# daq-beaglebone.net
KiCad netlist of a schematic drawn in EAGLE
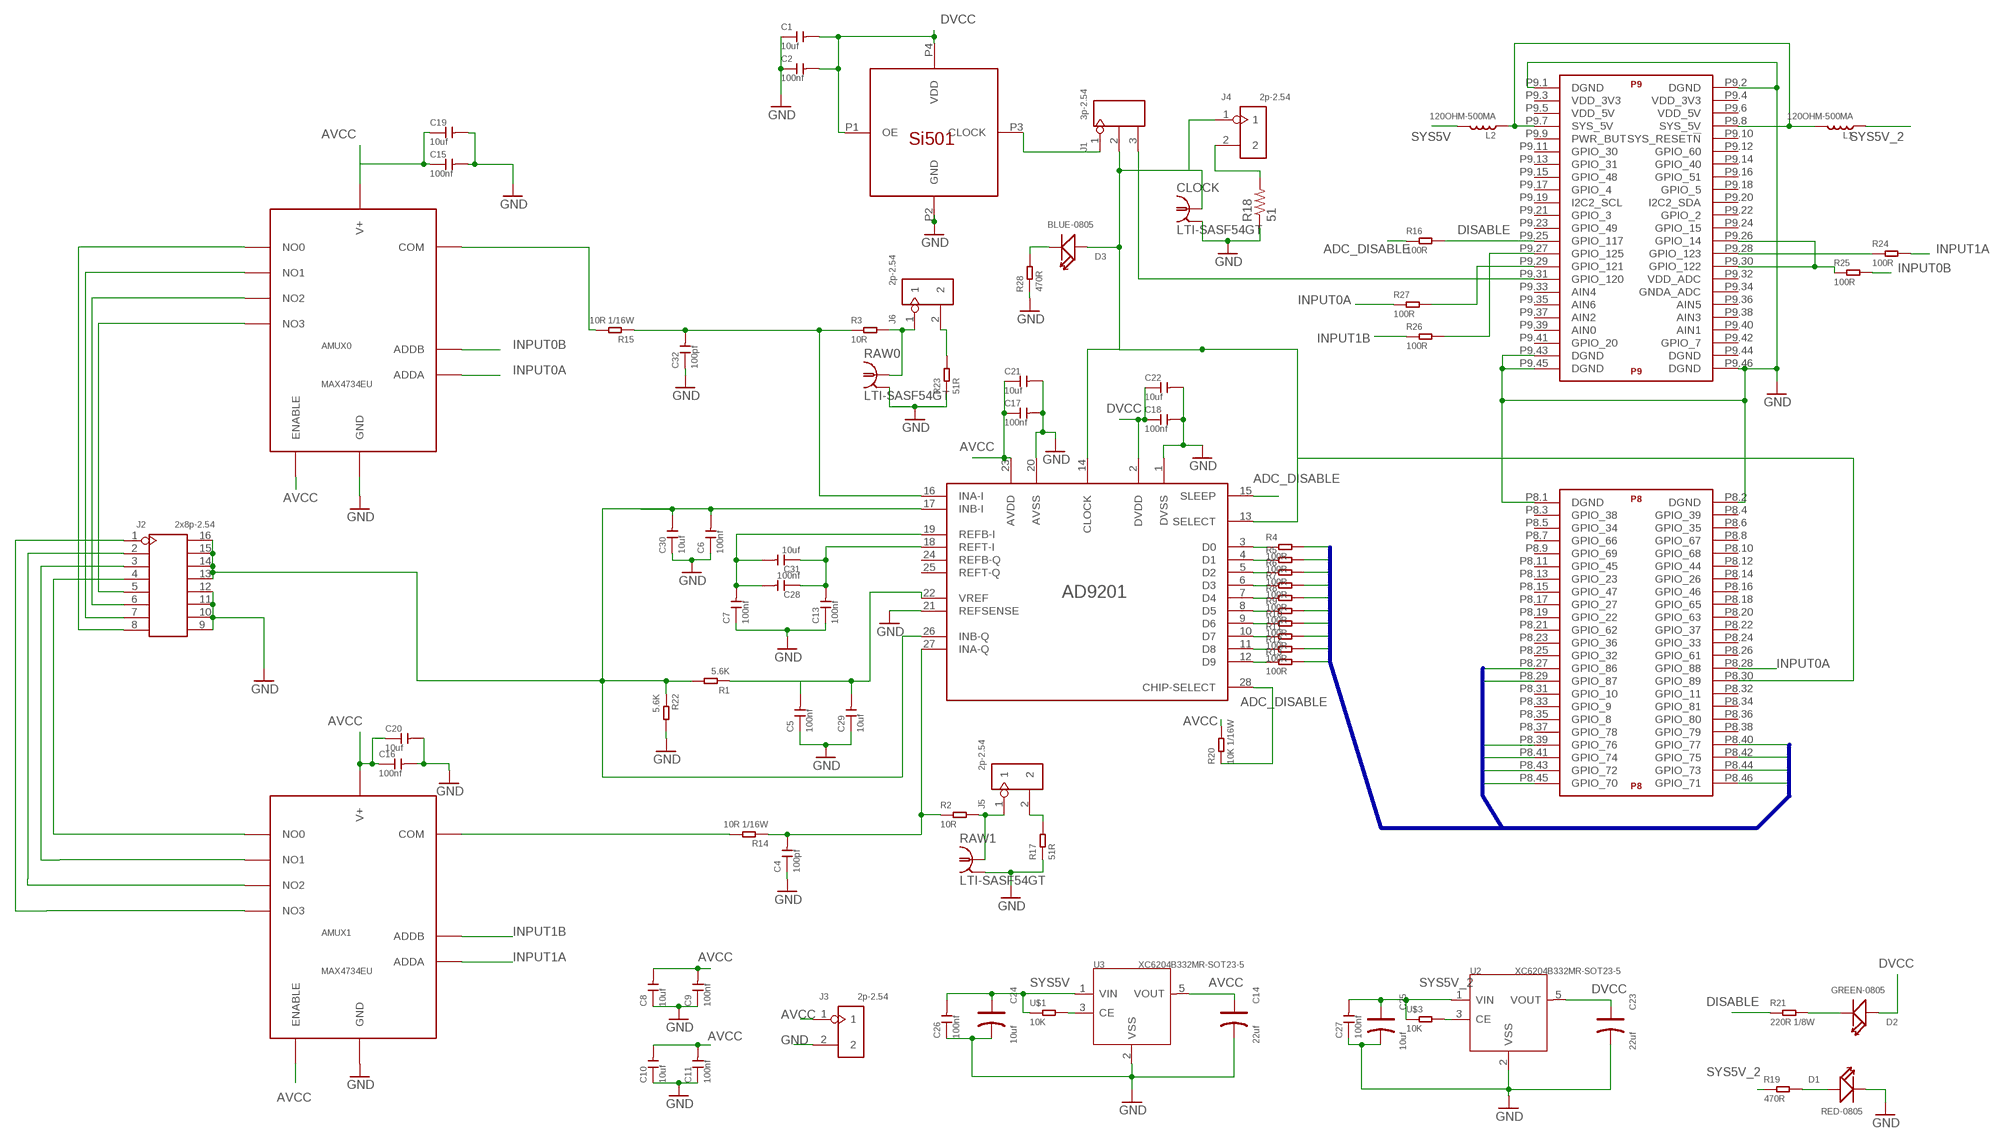
[diagram p0: schematic, sheet 1]

(export (version "E")
  (design (tool "Eeschema 10.0.6"))
  (components
    (comp (ref "AD9201")
      (value "AD9201")
      (footprint "eagle-import:SSOP28")
      (libsource (lib "eagle-import") (part "AD9201"))
    )
    (comp (ref "AMUX0")
      (value "MAX4734EU")
      (footprint "eagle-import:UMAX10")
      (libsource (lib "eagle-import") (part "MAX4734EU"))
    )
    (comp (ref "AMUX1")
      (value "MAX4734EU")
      (footprint "eagle-import:UMAX10")
      (libsource (lib "eagle-import") (part "MAX4734EU"))
    )
    (comp (ref "C1")
      (value "10uf")
      (footprint "eagle-import:C0402")
      (fields (field (name "MPN") "CC0402MRX5R5BB106"))
      (libsource (lib "eagle-import") (part "CERAMIC-10UF-6.3V-20%-X5R(0402)"))
    )
    (comp (ref "C2")
      (value "100nf")
      (footprint "eagle-import:C0402")
      (fields (field (name "MPN") "CC0402KRX7R8BB104"))
      (libsource (lib "eagle-import") (part "CERAMIC-100NF-25V-10%-X7R(0402)"))
    )
    (comp (ref "C4")
      (value "100pf")
      (footprint "eagle-import:C0402")
      (fields (field (name "MPN") "CC0402JRNPO9BN101"))
      (libsource (lib "eagle-import") (part "CERAMIC-100PF-50V-5%-NPO(0402)"))
    )
    (comp (ref "C5")
      (value "100nf")
      (footprint "eagle-import:C0402")
      (fields (field (name "MPN") "CC0402KRX7R8BB104"))
      (libsource (lib "eagle-import") (part "CERAMIC-100NF-25V-10%-X7R(0402)"))
    )
    (comp (ref "C6")
      (value "100nf")
      (footprint "eagle-import:C0402")
      (fields (field (name "MPN") "CC0402KRX7R8BB104"))
      (libsource (lib "eagle-import") (part "CERAMIC-100NF-25V-10%-X7R(0402)"))
    )
    (comp (ref "C7")
      (value "100nf")
      (footprint "eagle-import:C0402")
      (fields (field (name "MPN") "CC0402KRX7R8BB104"))
      (libsource (lib "eagle-import") (part "CERAMIC-100NF-25V-10%-X7R(0402)"))
    )
    (comp (ref "C8")
      (value "10uf")
      (footprint "eagle-import:C0402")
      (fields (field (name "MPN") "CC0402MRX5R5BB106"))
      (libsource (lib "eagle-import") (part "CERAMIC-10UF-6.3V-20%-X5R(0402)"))
    )
    (comp (ref "C9")
      (value "100nf")
      (footprint "eagle-import:C0402")
      (fields (field (name "MPN") "CC0402KRX7R8BB104"))
      (libsource (lib "eagle-import") (part "CERAMIC-100NF-25V-10%-X7R(0402)"))
    )
    (comp (ref "C10")
      (value "10uf")
      (footprint "eagle-import:C0402")
      (fields (field (name "MPN") "CC0402MRX5R5BB106"))
      (libsource (lib "eagle-import") (part "CERAMIC-10UF-6.3V-20%-X5R(0402)"))
    )
    (comp (ref "C11")
      (value "100nf")
      (footprint "eagle-import:C0402")
      (fields (field (name "MPN") "CC0402KRX7R8BB104"))
      (libsource (lib "eagle-import") (part "CERAMIC-100NF-25V-10%-X7R(0402)"))
    )
    (comp (ref "C13")
      (value "100nf")
      (footprint "eagle-import:C0402")
      (fields (field (name "MPN") "CC0402KRX7R8BB104"))
      (libsource (lib "eagle-import") (part "CERAMIC-100NF-25V-10%-X7R(0402)"))
    )
    (comp (ref "C14")
      (value "22uf")
      (footprint "eagle-import:AVX-A")
      (fields (field (name "MPN") "TAJA226K006RNJ"))
      (libsource (lib "eagle-import") (part "TANTALUM-SMD-22UF-6.3V(AVX-A)"))
    )
    (comp (ref "C15")
      (value "100nf")
      (footprint "eagle-import:C0402")
      (fields (field (name "MPN") "CC0402KRX7R8BB104"))
      (libsource (lib "eagle-import") (part "CERAMIC-100NF-25V-10%-X7R(0402)"))
    )
    (comp (ref "C16")
      (value "100nf")
      (footprint "eagle-import:C0402")
      (fields (field (name "MPN") "CC0402KRX7R8BB104"))
      (libsource (lib "eagle-import") (part "CERAMIC-100NF-25V-10%-X7R(0402)"))
    )
    (comp (ref "C17")
      (value "100nf")
      (footprint "eagle-import:C0402")
      (fields (field (name "MPN") "CC0402KRX7R8BB104"))
      (libsource (lib "eagle-import") (part "CERAMIC-100NF-25V-10%-X7R(0402)"))
    )
    (comp (ref "C18")
      (value "100nf")
      (footprint "eagle-import:C0402")
      (fields (field (name "MPN") "CC0402KRX7R8BB104"))
      (libsource (lib "eagle-import") (part "CERAMIC-100NF-25V-10%-X7R(0402)"))
    )
    (comp (ref "C19")
      (value "10uf")
      (footprint "eagle-import:C0402")
      (fields (field (name "MPN") "CC0402MRX5R5BB106"))
      (libsource (lib "eagle-import") (part "CERAMIC-10UF-6.3V-20%-X5R(0402)"))
    )
    (comp (ref "C20")
      (value "10uf")
      (footprint "eagle-import:C0402")
      (fields (field (name "MPN") "CC0402MRX5R5BB106"))
      (libsource (lib "eagle-import") (part "CERAMIC-10UF-6.3V-20%-X5R(0402)"))
    )
    (comp (ref "C21")
      (value "10uf")
      (footprint "eagle-import:C0402")
      (fields (field (name "MPN") "CC0402MRX5R5BB106"))
      (libsource (lib "eagle-import") (part "CERAMIC-10UF-6.3V-20%-X5R(0402)"))
    )
    (comp (ref "C22")
      (value "10uf")
      (footprint "eagle-import:C0402")
      (fields (field (name "MPN") "CC0402MRX5R5BB106"))
      (libsource (lib "eagle-import") (part "CERAMIC-10UF-6.3V-20%-X5R(0402)"))
    )
    (comp (ref "C23")
      (value "22uf")
      (footprint "eagle-import:AVX-A")
      (fields (field (name "MPN") "TAJA226K006RNJ"))
      (libsource (lib "eagle-import") (part "TANTALUM-SMD-22UF-6.3V(AVX-A)"))
    )
    (comp (ref "C24")
      (value "10uf")
      (footprint "eagle-import:AVX-A")
      (fields (field (name "MPN") "TAJA106K010RNJ"))
      (libsource (lib "eagle-import") (part "TANTALUM-SMD-10UF-10V-10%(AVX-A)"))
    )
    (comp (ref "C25")
      (value "10uf")
      (footprint "eagle-import:AVX-A")
      (fields (field (name "MPN") "TAJA106K010RNJ"))
      (libsource (lib "eagle-import") (part "TANTALUM-SMD-10UF-10V-10%(AVX-A)"))
    )
    (comp (ref "C26")
      (value "100nf")
      (footprint "eagle-import:C0402")
      (fields (field (name "MPN") "CC0402KRX7R8BB104"))
      (libsource (lib "eagle-import") (part "CERAMIC-100NF-25V-10%-X7R(0402)"))
    )
    (comp (ref "C27")
      (value "100nf")
      (footprint "eagle-import:C0402")
      (fields (field (name "MPN") "CC0402KRX7R8BB104"))
      (libsource (lib "eagle-import") (part "CERAMIC-100NF-25V-10%-X7R(0402)"))
    )
    (comp (ref "C28")
      (value "100nf")
      (footprint "eagle-import:C0402")
      (fields (field (name "MPN") "CC0402KRX7R8BB104"))
      (libsource (lib "eagle-import") (part "CERAMIC-100NF-25V-10%-X7R(0402)"))
    )
    (comp (ref "C29")
      (value "10uf")
      (footprint "eagle-import:C0402")
      (fields (field (name "MPN") "CC0402MRX5R5BB106"))
      (libsource (lib "eagle-import") (part "CERAMIC-10UF-6.3V-20%-X5R(0402)"))
    )
    (comp (ref "C30")
      (value "10uf")
      (footprint "eagle-import:C0402")
      (fields (field (name "MPN") "CC0402MRX5R5BB106"))
      (libsource (lib "eagle-import") (part "CERAMIC-10UF-6.3V-20%-X5R(0402)"))
    )
    (comp (ref "C31")
      (value "10uf")
      (footprint "eagle-import:C0402")
      (fields (field (name "MPN") "CC0402MRX5R5BB106"))
      (libsource (lib "eagle-import") (part "CERAMIC-10UF-6.3V-20%-X5R(0402)"))
    )
    (comp (ref "C32")
      (value "100pf")
      (footprint "eagle-import:C0402")
      (fields (field (name "MPN") "CC0402JRNPO9BN101"))
      (libsource (lib "eagle-import") (part "CERAMIC-100PF-50V-5%-NPO(0402)"))
    )
    (comp (ref "CLOCK")
      (value "LTI-SASF54GT")
      (footprint "eagle-import:LTI-SASF54GT")
      (libsource (lib "eagle-import") (part "LTI-SASF54GT"))
    )
    (comp (ref "D1")
      (value "RED-0805")
      (footprint "eagle-import:LED-0805")
      (fields (field (name "MPN") "17-215SURC/S530-A2/TR8"))
      (libsource (lib "eagle-import") (part "SMD-LED-CLEAR-RED(0805)"))
    )
    (comp (ref "D2")
      (value "GREEN-0805")
      (footprint "eagle-import:LED-0805")
      (fields (field (name "MPN") "17-215SYGC/S530-E2/TR8"))
      (libsource (lib "eagle-import") (part "SMD-LED-CLEAR-GREEN(0805)"))
    )
    (comp (ref "D3")
      (value "BLUE-0805")
      (footprint "eagle-import:LED-0805")
      (fields (field (name "MPN") "17-215SURC/S530-A2/TR8"))
      (libsource (lib "eagle-import") (part "SMD-LED-CLEAR-RED(0805)"))
    )
    (comp (ref "J1")
      (value "3p-2.54")
      (footprint "eagle-import:H3-2.54")
      (fields (field (name "MPN") "F185-1103A0BSYA1"))
      (libsource (lib "eagle-import") (part "DIP-BLACK-FEMALE-HEADER-VERT(3P-2.54)"))
    )
    (comp (ref "J2")
      (value "2x8p-2.54")
      (footprint "eagle-import:H2X8-2.54")
      (fields (field (name "MPN") "F185-1216A0BSYA1"))
      (libsource (lib "eagle-import") (part "DIP-BLACK-FEMALE-HEADER-VERT(2X8P-2.54)"))
    )
    (comp (ref "J3")
      (value "2p-2.54")
      (footprint "eagle-import:H2-2.54")
      (fields (field (name "MPN") "F185-1102A1BSYA1"))
      (libsource (lib "eagle-import") (part "DIP-BLACK-FEMALE-HEADER-VERT(2P-2.54)"))
    )
    (comp (ref "J4")
      (value "2p-2.54")
      (footprint "eagle-import:H2-2.54")
      (fields (field (name "MPN") "P125-1102A0BS116A1"))
      (libsource (lib "eagle-import") (part "DIP-BLACK-MALE-HEADER-VERT(2P-2.54)"))
    )
    (comp (ref "J5")
      (value "2p-2.54")
      (footprint "eagle-import:H2-2.54")
      (fields (field (name "MPN") "P125-1102A0BS116A1"))
      (libsource (lib "eagle-import") (part "DIP-BLACK-MALE-HEADER-VERT(2P-2.54)"))
    )
    (comp (ref "J6")
      (value "2p-2.54")
      (footprint "eagle-import:H2-2.54")
      (fields (field (name "MPN") "P125-1102A0BS116A1"))
      (libsource (lib "eagle-import") (part "DIP-BLACK-MALE-HEADER-VERT(2P-2.54)"))
    )
    (comp (ref "L1")
      (value "120OHM-500MA")
      (footprint "eagle-import:L0603")
      (fields (field (name "MPN") "BLM18AG121SN1D"))
      (libsource (lib "eagle-import") (part "SMD-FERRITE-CHIP-120-OHM-500MA(0603)"))
    )
    (comp (ref "L2")
      (value "120OHM-500MA")
      (footprint "eagle-import:L0603")
      (fields (field (name "MPN") "BLM18AG121SN1D"))
      (libsource (lib "eagle-import") (part "SMD-FERRITE-CHIP-120-OHM-500MA(0603)"))
    )
    (comp (ref "R1")
      (value "5.6K")
      (footprint "eagle-import:R0402")
      (fields (field (name "MPN") "CRCW04025K60FKED"))
      (libsource (lib "eagle-import") (part "SMD-RES-5.6K-1%-1/10W(0402)"))
    )
    (comp (ref "R2")
      (value "10R")
      (footprint "eagle-import:R0402")
      (fields (field (name "MPN") "RC0402JR-070RL"))
      (libsource (lib "eagle-import") (part "SMD-RES-0R-5%-1/16W(0402)"))
    )
    (comp (ref "R3")
      (value "10R")
      (footprint "eagle-import:R0402")
      (fields (field (name "MPN") "RC0402JR-070RL"))
      (libsource (lib "eagle-import") (part "SMD-RES-0R-5%-1/16W(0402)"))
    )
    (comp (ref "R4")
      (value "100R")
      (footprint "eagle-import:R0402")
      (fields (field (name "MPN") "RC0402JR-07100RL"))
      (libsource (lib "eagle-import") (part "SMD-RES-100R-5%-1/16W(0402)"))
    )
    (comp (ref "R5")
      (value "100R")
      (footprint "eagle-import:R0402")
      (fields (field (name "MPN") "RC0402JR-07100RL"))
      (libsource (lib "eagle-import") (part "SMD-RES-100R-5%-1/16W(0402)"))
    )
    (comp (ref "R6")
      (value "100R")
      (footprint "eagle-import:R0402")
      (fields (field (name "MPN") "RC0402JR-07100RL"))
      (libsource (lib "eagle-import") (part "SMD-RES-100R-5%-1/16W(0402)"))
    )
    (comp (ref "R7")
      (value "100R")
      (footprint "eagle-import:R0402")
      (fields (field (name "MPN") "RC0402JR-07100RL"))
      (libsource (lib "eagle-import") (part "SMD-RES-100R-5%-1/16W(0402)"))
    )
    (comp (ref "R8")
      (value "100R")
      (footprint "eagle-import:R0402")
      (fields (field (name "MPN") "RC0402JR-07100RL"))
      (libsource (lib "eagle-import") (part "SMD-RES-100R-5%-1/16W(0402)"))
    )
    (comp (ref "R9")
      (value "100R")
      (footprint "eagle-import:R0402")
      (fields (field (name "MPN") "RC0402JR-07100RL"))
      (libsource (lib "eagle-import") (part "SMD-RES-100R-5%-1/16W(0402)"))
    )
    (comp (ref "R10")
      (value "100R")
      (footprint "eagle-import:R0402")
      (fields (field (name "MPN") "RC0402JR-07100RL"))
      (libsource (lib "eagle-import") (part "SMD-RES-100R-5%-1/16W(0402)"))
    )
    (comp (ref "R11")
      (value "100R")
      (footprint "eagle-import:R0402")
      (fields (field (name "MPN") "RC0402JR-07100RL"))
      (libsource (lib "eagle-import") (part "SMD-RES-100R-5%-1/16W(0402)"))
    )
    (comp (ref "R12")
      (value "100R")
      (footprint "eagle-import:R0402")
      (fields (field (name "MPN") "RC0402JR-07100RL"))
      (libsource (lib "eagle-import") (part "SMD-RES-100R-5%-1/16W(0402)"))
    )
    (comp (ref "R13")
      (value "100R")
      (footprint "eagle-import:R0402")
      (fields (field (name "MPN") "RC0402JR-07100RL"))
      (libsource (lib "eagle-import") (part "SMD-RES-100R-5%-1/16W(0402)"))
    )
    (comp (ref "R14")
      (value "10R 1/16W")
      (footprint "eagle-import:R0402")
      (fields (field (name "MPN") "RC0402FR-0710RL"))
      (libsource (lib "eagle-import") (part "SMD-RES-10R-1%-1/16W(0402)"))
    )
    (comp (ref "R15")
      (value "10R 1/16W")
      (footprint "eagle-import:R0402")
      (fields (field (name "MPN") "RC0402FR-0710RL"))
      (libsource (lib "eagle-import") (part "SMD-RES-10R-1%-1/16W(0402)"))
    )
    (comp (ref "R16")
      (value "100R")
      (footprint "eagle-import:R0402")
      (fields (field (name "MPN") "RC0402JR-07100RL"))
      (libsource (lib "eagle-import") (part "SMD-RES-100R-5%-1/16W(0402)"))
    )
    (comp (ref "R17")
      (value "51R")
      (footprint "eagle-import:R0603")
      (fields (field (name "MPN") "RC0603FR-0751RL"))
      (libsource (lib "eagle-import") (part "SMD-RES-51R-1%-1/10W(0603)"))
    )
    (comp (ref "R18")
      (value "51")
      (footprint "eagle-import:R1206")
      (libsource (lib "eagle-import") (part "R-US_R1206"))
    )
    (comp (ref "R19")
      (value "470R")
      (footprint "eagle-import:R0402")
      (fields (field (name "MPN") "RC0402FR-07470RL"))
      (libsource (lib "eagle-import") (part "SMD-RES-470R-1%-1/16W(0402)"))
    )
    (comp (ref "R20")
      (value "10K 1/16W")
      (footprint "eagle-import:R0402")
      (fields (field (name "MPN") "RC0402FR-0710KL"))
      (libsource (lib "eagle-import") (part "SMD-RES-10K-1%-1/16W(0402)"))
    )
    (comp (ref "R21")
      (value "220R 1/8W")
      (footprint "eagle-import:R0402")
      (fields (field (name "MPN") "RC0402FR-07220RL"))
      (libsource (lib "eagle-import") (part "SMD-RES-220R-1%-1/8W(0402)"))
    )
    (comp (ref "R22")
      (value "5.6K")
      (footprint "eagle-import:R0402")
      (fields (field (name "MPN") "CRCW04025K60FKED"))
      (libsource (lib "eagle-import") (part "SMD-RES-5.6K-1%-1/10W(0402)"))
    )
    (comp (ref "R23")
      (value "51R")
      (footprint "eagle-import:R0603")
      (fields (field (name "MPN") "RC0603FR-0751RL"))
      (libsource (lib "eagle-import") (part "SMD-RES-51R-1%-1/10W(0603)"))
    )
    (comp (ref "R24")
      (value "100R")
      (footprint "eagle-import:R0402")
      (fields (field (name "MPN") "RC0402FR-0733RL"))
      (libsource (lib "eagle-import") (part "SMD-RES-33R-1%-1/16W(0402)"))
    )
    (comp (ref "R25")
      (value "100R")
      (footprint "eagle-import:R0402")
      (fields (field (name "MPN") "RC0402FR-0733RL"))
      (libsource (lib "eagle-import") (part "SMD-RES-33R-1%-1/16W(0402)"))
    )
    (comp (ref "R26")
      (value "100R")
      (footprint "eagle-import:R0402")
      (fields (field (name "MPN") "RC0402FR-0733RL"))
      (libsource (lib "eagle-import") (part "SMD-RES-33R-1%-1/16W(0402)"))
    )
    (comp (ref "R27")
      (value "100R")
      (footprint "eagle-import:R0402")
      (fields (field (name "MPN") "RC0402FR-0733RL"))
      (libsource (lib "eagle-import") (part "SMD-RES-33R-1%-1/16W(0402)"))
    )
    (comp (ref "R28")
      (value "470R")
      (footprint "eagle-import:R0402")
      (fields (field (name "MPN") "RC0402FR-07470RL"))
      (libsource (lib "eagle-import") (part "SMD-RES-470R-1%-1/16W(0402)"))
    )
    (comp (ref "RAW0")
      (value "LTI-SASF54GT")
      (footprint "eagle-import:LTI-SASF54GT")
      (libsource (lib "eagle-import") (part "LTI-SASF54GT"))
    )
    (comp (ref "RAW1")
      (value "LTI-SASF54GT")
      (footprint "eagle-import:LTI-SASF54GT")
      (libsource (lib "eagle-import") (part "LTI-SASF54GT"))
    )
    (comp (ref "U$1")
      (value "10K")
      (footprint "eagle-import:R0402")
      (fields (field (name "MPN") "RC0402JR-0710KL"))
      (libsource (lib "eagle-import") (part "SMD-RES-10K-5%-1/(0402)"))
    )
    (comp (ref "U$2")
      (value "BEAGLE_BONE_BLACK_CAPE")
      (footprint "eagle-import:BEAGLE_BONE_BLACK_CAPE")
      (libsource (lib "eagle-import") (part "BEAGLE_BONE_BLACK_CAPE"))
    )
    (comp (ref "U$3")
      (value "10K")
      (footprint "eagle-import:R0402")
      (fields (field (name "MPN") "RC0402JR-0710KL"))
      (libsource (lib "eagle-import") (part "SMD-RES-10K-5%-1/(0402)"))
    )
    (comp (ref "U$4")
      (value "SI501")
      (footprint "eagle-import:2X2.5DFN")
      (libsource (lib "eagle-import") (part "SI501"))
    )
    (comp (ref "U2")
      (value "XC6204B332MR-SOT23-5")
      (footprint "eagle-import:SOT-23-5")
      (fields (field (name "MPN") "XC6204B332MR"))
      (libsource (lib "eagle-import") (part "PMIC-XC6204B332MR(SOT23-5)"))
    )
    (comp (ref "U3")
      (value "XC6204B332MR-SOT23-5")
      (footprint "eagle-import:SOT-23-5")
      (fields (field (name "MPN") "XC6204B332MR"))
      (libsource (lib "eagle-import") (part "PMIC-XC6204B332MR(SOT23-5)"))
    )
  )
  (nets
    (net (code "1") (name "/ADC_DISABLE") (class "Default")
      (node (ref "AD9201") (pin "15") (pinfunction "SLEEP_15") (pintype "input"))
      (node (ref "AD9201") (pin "28") (pinfunction "CHIP-SELECT_28") (pintype "input"))
      (node (ref "R16") (pin "1") (pinfunction "1_1") (pintype "passive"))
      (node (ref "R20") (pin "1") (pinfunction "1_1") (pintype "passive"))
    )
    (net (code "2") (name "/AVCC") (class "Default")
      (node (ref "AD9201") (pin "23") (pinfunction "AVDD_23") (pintype "power_in"))
      (node (ref "AMUX0") (pin "P$5") (pinfunction "ENABLE_P$5") (pintype "bidirectional"))
      (node (ref "AMUX0") (pin "P$6") (pinfunction "V+_P$6") (pintype "bidirectional"))
      (node (ref "AMUX1") (pin "P$5") (pinfunction "ENABLE_P$5") (pintype "bidirectional"))
      (node (ref "AMUX1") (pin "P$6") (pinfunction "V+_P$6") (pintype "bidirectional"))
      (node (ref "C10") (pin "2") (pinfunction "2_2") (pintype "passive"))
      (node (ref "C11") (pin "2") (pinfunction "2_2") (pintype "passive"))
      (node (ref "C14") (pin "+") (pinfunction "+_+") (pintype "passive"))
      (node (ref "C15") (pin "1") (pinfunction "1_1") (pintype "passive"))
      (node (ref "C16") (pin "1") (pinfunction "1_1") (pintype "passive"))
      (node (ref "C17") (pin "1") (pinfunction "1_1") (pintype "passive"))
      (node (ref "C19") (pin "1") (pinfunction "1_1") (pintype "passive"))
      (node (ref "C20") (pin "1") (pinfunction "1_1") (pintype "passive"))
      (node (ref "C21") (pin "1") (pinfunction "1_1") (pintype "passive"))
      (node (ref "C8") (pin "2") (pinfunction "2_2") (pintype "passive"))
      (node (ref "C9") (pin "2") (pinfunction "2_2") (pintype "passive"))
      (node (ref "J3") (pin "1") (pinfunction "1_1") (pintype "bidirectional"))
      (node (ref "R20") (pin "2") (pinfunction "2_2") (pintype "passive"))
      (node (ref "U3") (pin "5") (pinfunction "VOUT_5") (pintype "bidirectional"))
    )
    (net (code "3") (name "/D0") (class "Default")
      (node (ref "R4") (pin "2") (pinfunction "2_2") (pintype "passive"))
      (node (ref "U$2") (pin "P8.45") (pinfunction "GPIO_70_P8.45") (pintype "bidirectional"))
    )
    (net (code "4") (name "/D1") (class "Default")
      (node (ref "R5") (pin "2") (pinfunction "2_2") (pintype "passive"))
      (node (ref "U$2") (pin "P8.46") (pinfunction "GPIO_71_P8.46") (pintype "bidirectional"))
    )
    (net (code "5") (name "/D2") (class "Default")
      (node (ref "R6") (pin "2") (pinfunction "2_2") (pintype "passive"))
      (node (ref "U$2") (pin "P8.43") (pinfunction "GPIO_72_P8.43") (pintype "bidirectional"))
    )
    (net (code "6") (name "/D3") (class "Default")
      (node (ref "R7") (pin "2") (pinfunction "2_2") (pintype "passive"))
      (node (ref "U$2") (pin "P8.44") (pinfunction "GPIO_73_P8.44") (pintype "bidirectional"))
    )
    (net (code "7") (name "/D4") (class "Default")
      (node (ref "R8") (pin "2") (pinfunction "2_2") (pintype "passive"))
      (node (ref "U$2") (pin "P8.41") (pinfunction "GPIO_74_P8.41") (pintype "bidirectional"))
    )
    (net (code "8") (name "/D5") (class "Default")
      (node (ref "R9") (pin "2") (pinfunction "2_2") (pintype "passive"))
      (node (ref "U$2") (pin "P8.42") (pinfunction "GPIO_75_P8.42") (pintype "bidirectional"))
    )
    (net (code "9") (name "/D6") (class "Default")
      (node (ref "R10") (pin "2") (pinfunction "2_2") (pintype "passive"))
      (node (ref "U$2") (pin "P8.39") (pinfunction "GPIO_76_P8.39") (pintype "bidirectional"))
    )
    (net (code "10") (name "/D7") (class "Default")
      (node (ref "R11") (pin "2") (pinfunction "2_2") (pintype "passive"))
      (node (ref "U$2") (pin "P8.40") (pinfunction "GPIO_77_P8.40") (pintype "bidirectional"))
    )
    (net (code "11") (name "/D8") (class "Default")
      (node (ref "R12") (pin "2") (pinfunction "2_2") (pintype "passive"))
      (node (ref "U$2") (pin "P8.27") (pinfunction "GPIO_86_P8.27") (pintype "bidirectional"))
    )
    (net (code "12") (name "/D9") (class "Default")
      (node (ref "R13") (pin "2") (pinfunction "2_2") (pintype "passive"))
      (node (ref "U$2") (pin "P8.29") (pinfunction "GPIO_87_P8.29") (pintype "bidirectional"))
    )
    (net (code "13") (name "/DISABLE") (class "Default")
      (node (ref "R16") (pin "2") (pinfunction "2_2") (pintype "passive"))
      (node (ref "R21") (pin "1") (pinfunction "1_1") (pintype "passive"))
      (node (ref "U$2") (pin "P9.25") (pinfunction "GPIO_117_P9.25") (pintype "bidirectional"))
    )
    (net (code "14") (name "/DVCC") (class "Default")
      (node (ref "AD9201") (pin "2") (pinfunction "DVDD_2") (pintype "power_in"))
      (node (ref "C1") (pin "2") (pinfunction "2_2") (pintype "passive"))
      (node (ref "C18") (pin "1") (pinfunction "1_1") (pintype "passive"))
      (node (ref "C2") (pin "2") (pinfunction "2_2") (pintype "passive"))
      (node (ref "C22") (pin "1") (pinfunction "1_1") (pintype "passive"))
      (node (ref "C23") (pin "+") (pinfunction "+_+") (pintype "passive"))
      (node (ref "D2") (pin "+") (pinfunction "+_+") (pintype "passive"))
      (node (ref "U$4") (pin "P1") (pinfunction "OE_P1") (pintype "bidirectional"))
      (node (ref "U$4") (pin "P4") (pinfunction "VDD_P4") (pintype "bidirectional"))
      (node (ref "U2") (pin "5") (pinfunction "VOUT_5") (pintype "bidirectional"))
    )
    (net (code "15") (name "/INPUT0A") (class "Default")
      (node (ref "AMUX0") (pin "P$1") (pinfunction "ADDA_P$1") (pintype "bidirectional"))
      (node (ref "R27") (pin "1") (pinfunction "1_1") (pintype "passive"))
      (node (ref "U$2") (pin "P8.28") (pinfunction "GPIO_88_P8.28") (pintype "bidirectional"))
    )
    (net (code "16") (name "/INPUT0B") (class "Default")
      (node (ref "AMUX0") (pin "P$10") (pinfunction "ADDB_P$10") (pintype "bidirectional"))
      (node (ref "R25") (pin "2") (pinfunction "2_2") (pintype "passive"))
    )
    (net (code "17") (name "/INPUT1A") (class "Default")
      (node (ref "AMUX1") (pin "P$1") (pinfunction "ADDA_P$1") (pintype "bidirectional"))
      (node (ref "R24") (pin "2") (pinfunction "2_2") (pintype "passive"))
    )
    (net (code "18") (name "/INPUT1B") (class "Default")
      (node (ref "AMUX1") (pin "P$10") (pinfunction "ADDB_P$10") (pintype "bidirectional"))
      (node (ref "R26") (pin "1") (pinfunction "1_1") (pintype "passive"))
    )
    (net (code "19") (name "/SYS5V") (class "Default")
      (node (ref "C24") (pin "+") (pinfunction "+_+") (pintype "passive"))
      (node (ref "C26") (pin "2") (pinfunction "2_2") (pintype "passive"))
      (node (ref "L2") (pin "2") (pinfunction "2_2") (pintype "passive"))
      (node (ref "U$1") (pin "1") (pinfunction "1_1") (pintype "passive"))
      (node (ref "U3") (pin "1") (pinfunction "VIN_1") (pintype "bidirectional"))
    )
    (net (code "20") (name "/SYS5V_2") (class "Default")
      (node (ref "C25") (pin "+") (pinfunction "+_+") (pintype "passive"))
      (node (ref "C27") (pin "2") (pinfunction "2_2") (pintype "passive"))
      (node (ref "L1") (pin "1") (pinfunction "1_1") (pintype "passive"))
      (node (ref "R19") (pin "1") (pinfunction "1_1") (pintype "passive"))
      (node (ref "U$3") (pin "1") (pinfunction "1_1") (pintype "passive"))
      (node (ref "U2") (pin "1") (pinfunction "VIN_1") (pintype "bidirectional"))
    )
    (net (code "21") (name "GND") (class "Default")
      (node (ref "AD9201") (pin "1") (pinfunction "DVSS_1") (pintype "power_in"))
      (node (ref "AD9201") (pin "20") (pinfunction "AVSS_20") (pintype "power_in"))
      (node (ref "AD9201") (pin "21") (pinfunction "REFSENSE_21") (pintype "input"))
      (node (ref "AMUX0") (pin "P$3") (pinfunction "GND_P$3") (pintype "bidirectional"))
      (node (ref "AMUX1") (pin "P$3") (pinfunction "GND_P$3") (pintype "bidirectional"))
      (node (ref "C1") (pin "1") (pinfunction "1_1") (pintype "passive"))
      (node (ref "C10") (pin "1") (pinfunction "1_1") (pintype "passive"))
      (node (ref "C11") (pin "1") (pinfunction "1_1") (pintype "passive"))
      (node (ref "C13") (pin "1") (pinfunction "1_1") (pintype "passive"))
      (node (ref "C14") (pin "-") (pinfunction "-_-") (pintype "passive"))
      (node (ref "C15") (pin "2") (pinfunction "2_2") (pintype "passive"))
      (node (ref "C16") (pin "2") (pinfunction "2_2") (pintype "passive"))
      (node (ref "C17") (pin "2") (pinfunction "2_2") (pintype "passive"))
      (node (ref "C18") (pin "2") (pinfunction "2_2") (pintype "passive"))
      (node (ref "C19") (pin "2") (pinfunction "2_2") (pintype "passive"))
      (node (ref "C2") (pin "1") (pinfunction "1_1") (pintype "passive"))
      (node (ref "C20") (pin "2") (pinfunction "2_2") (pintype "passive"))
      (node (ref "C21") (pin "2") (pinfunction "2_2") (pintype "passive"))
      (node (ref "C22") (pin "2") (pinfunction "2_2") (pintype "passive"))
      (node (ref "C23") (pin "-") (pinfunction "-_-") (pintype "passive"))
      (node (ref "C24") (pin "-") (pinfunction "-_-") (pintype "passive"))
      (node (ref "C25") (pin "-") (pinfunction "-_-") (pintype "passive"))
      (node (ref "C26") (pin "1") (pinfunction "1_1") (pintype "passive"))
      (node (ref "C27") (pin "1") (pinfunction "1_1") (pintype "passive"))
      (node (ref "C29") (pin "1") (pinfunction "1_1") (pintype "passive"))
      (node (ref "C30") (pin "1") (pinfunction "1_1") (pintype "passive"))
      (node (ref "C32") (pin "1") (pinfunction "1_1") (pintype "passive"))
      (node (ref "C4") (pin "1") (pinfunction "1_1") (pintype "passive"))
      (node (ref "C5") (pin "1") (pinfunction "1_1") (pintype "passive"))
      (node (ref "C6") (pin "1") (pinfunction "1_1") (pintype "passive"))
      (node (ref "C7") (pin "1") (pinfunction "1_1") (pintype "passive"))
      (node (ref "C8") (pin "1") (pinfunction "1_1") (pintype "passive"))
      (node (ref "C9") (pin "1") (pinfunction "1_1") (pintype "passive"))
      (node (ref "CLOCK") (pin "2") (pinfunction "2_2") (pintype "passive"))
      (node (ref "CLOCK") (pin "3") (pinfunction "2_3") (pintype "passive"))
      (node (ref "CLOCK") (pin "4") (pinfunction "2_4") (pintype "passive"))
      (node (ref "CLOCK") (pin "5") (pinfunction "2_5") (pintype "passive"))
      (node (ref "D1") (pin "-") (pinfunction "-_-") (pintype "passive"))
      (node (ref "J2") (pin "10") (pinfunction "10_10") (pintype "bidirectional"))
      (node (ref "J2") (pin "11") (pinfunction "11_11") (pintype "bidirectional"))
      (node (ref "J2") (pin "12") (pinfunction "12_12") (pintype "bidirectional"))
      (node (ref "J2") (pin "9") (pinfunction "9_9") (pintype "bidirectional"))
      (node (ref "J3") (pin "2") (pinfunction "2_2") (pintype "bidirectional"))
      (node (ref "R17") (pin "1") (pinfunction "1_1") (pintype "passive"))
      (node (ref "R18") (pin "1") (pinfunction "1_1") (pintype "passive"))
      (node (ref "R22") (pin "2") (pinfunction "2_2") (pintype "passive"))
      (node (ref "R23") (pin "1") (pinfunction "1_1") (pintype "passive"))
      (node (ref "R28") (pin "1") (pinfunction "1_1") (pintype "passive"))
      (node (ref "RAW0") (pin "2") (pinfunction "2_2") (pintype "passive"))
      (node (ref "RAW0") (pin "3") (pinfunction "2_3") (pintype "passive"))
      (node (ref "RAW0") (pin "4") (pinfunction "2_4") (pintype "passive"))
      (node (ref "RAW0") (pin "5") (pinfunction "2_5") (pintype "passive"))
      (node (ref "RAW1") (pin "2") (pinfunction "2_2") (pintype "passive"))
      (node (ref "RAW1") (pin "3") (pinfunction "2_3") (pintype "passive"))
      (node (ref "RAW1") (pin "4") (pinfunction "2_4") (pintype "passive"))
      (node (ref "RAW1") (pin "5") (pinfunction "2_5") (pintype "passive"))
      (node (ref "U$2") (pin "P8.1") (pinfunction "DGND_P8.1") (pintype "bidirectional"))
      (node (ref "U$2") (pin "P8.2") (pinfunction "DGND_P8.2") (pintype "bidirectional"))
      (node (ref "U$2") (pin "P9.1") (pinfunction "DGND_P9.1") (pintype "bidirectional"))
      (node (ref "U$2") (pin "P9.2") (pinfunction "DGND_P9.2") (pintype "bidirectional"))
      (node (ref "U$2") (pin "P9.43") (pinfunction "DGND_P9.43") (pintype "bidirectional"))
      (node (ref "U$2") (pin "P9.45") (pinfunction "DGND_P9.45") (pintype "bidirectional"))
      (node (ref "U$2") (pin "P9.46") (pinfunction "DGND_P9.46") (pintype "bidirectional"))
      (node (ref "U$4") (pin "P2") (pinfunction "GND_P2") (pintype "bidirectional"))
      (node (ref "U2") (pin "2") (pinfunction "VSS_2") (pintype "bidirectional"))
      (node (ref "U3") (pin "2") (pinfunction "VSS_2") (pintype "bidirectional"))
    )
    (net (code "22") (name "Net-(AD9201-CLOCK)") (class "Default")
      (node (ref "AD9201") (pin "13") (pinfunction "SELECT_13") (pintype "input"))
      (node (ref "AD9201") (pin "14") (pinfunction "CLOCK_14") (pintype "input"))
      (node (ref "CLOCK") (pin "1") (pinfunction "1_1") (pintype "passive"))
      (node (ref "D3") (pin "+") (pinfunction "+_+") (pintype "passive"))
      (node (ref "J1") (pin "2") (pinfunction "P$2_2") (pintype "bidirectional"))
      (node (ref "J4") (pin "1") (pinfunction "1_1") (pintype "bidirectional"))
      (node (ref "U$2") (pin "P8.30") (pinfunction "GPIO_89_P8.30") (pintype "bidirectional"))
    )
    (net (code "23") (name "Net-(AD9201-D0)") (class "Default")
      (node (ref "AD9201") (pin "3") (pinfunction "D0_3") (pintype "output"))
      (node (ref "R4") (pin "1") (pinfunction "1_1") (pintype "passive"))
    )
    (net (code "24") (name "Net-(AD9201-D1)") (class "Default")
      (node (ref "AD9201") (pin "4") (pinfunction "D1_4") (pintype "output"))
      (node (ref "R5") (pin "1") (pinfunction "1_1") (pintype "passive"))
    )
    (net (code "25") (name "Net-(AD9201-D2)") (class "Default")
      (node (ref "AD9201") (pin "5") (pinfunction "D2_5") (pintype "output"))
      (node (ref "R6") (pin "1") (pinfunction "1_1") (pintype "passive"))
    )
    (net (code "26") (name "Net-(AD9201-D3)") (class "Default")
      (node (ref "AD9201") (pin "6") (pinfunction "D3_6") (pintype "output"))
      (node (ref "R7") (pin "1") (pinfunction "1_1") (pintype "passive"))
    )
    (net (code "27") (name "Net-(AD9201-D4)") (class "Default")
      (node (ref "AD9201") (pin "7") (pinfunction "D4_7") (pintype "output"))
      (node (ref "R8") (pin "1") (pinfunction "1_1") (pintype "passive"))
    )
    (net (code "28") (name "Net-(AD9201-D5)") (class "Default")
      (node (ref "AD9201") (pin "8") (pinfunction "D5_8") (pintype "output"))
      (node (ref "R9") (pin "1") (pinfunction "1_1") (pintype "passive"))
    )
    (net (code "29") (name "Net-(AD9201-D6)") (class "Default")
      (node (ref "AD9201") (pin "9") (pinfunction "D6_9") (pintype "output"))
      (node (ref "R10") (pin "1") (pinfunction "1_1") (pintype "passive"))
    )
    (net (code "30") (name "Net-(AD9201-D7)") (class "Default")
      (node (ref "AD9201") (pin "10") (pinfunction "D7_10") (pintype "output"))
      (node (ref "R11") (pin "1") (pinfunction "1_1") (pintype "passive"))
    )
    (net (code "31") (name "Net-(AD9201-D8)") (class "Default")
      (node (ref "AD9201") (pin "11") (pinfunction "D8_11") (pintype "output"))
      (node (ref "R12") (pin "1") (pinfunction "1_1") (pintype "passive"))
    )
    (net (code "32") (name "Net-(AD9201-D9)") (class "Default")
      (node (ref "AD9201") (pin "12") (pinfunction "D9_12") (pintype "output"))
      (node (ref "R13") (pin "1") (pinfunction "1_1") (pintype "passive"))
    )
    (net (code "33") (name "Net-(AD9201-INA-I)") (class "Default")
      (node (ref "AD9201") (pin "16") (pinfunction "INA-I_16") (pintype "input"))
      (node (ref "C32") (pin "2") (pinfunction "2_2") (pintype "passive"))
      (node (ref "R15") (pin "1") (pinfunction "1_1") (pintype "passive"))
      (node (ref "R3") (pin "1") (pinfunction "1_1") (pintype "passive"))
    )
    (net (code "34") (name "Net-(AD9201-INA-Q)") (class "Default")
      (node (ref "AD9201") (pin "27") (pinfunction "INA-Q_27") (pintype "input"))
      (node (ref "C4") (pin "2") (pinfunction "2_2") (pintype "passive"))
      (node (ref "R14") (pin "1") (pinfunction "1_1") (pintype "passive"))
      (node (ref "R2") (pin "1") (pinfunction "1_1") (pintype "passive"))
    )
    (net (code "35") (name "Net-(AD9201-INB-I)") (class "Default")
      (node (ref "AD9201") (pin "17") (pinfunction "INB-I_17") (pintype "input"))
      (node (ref "AD9201") (pin "26") (pinfunction "INB-Q_26") (pintype "input"))
      (node (ref "C30") (pin "2") (pinfunction "2_2") (pintype "passive"))
      (node (ref "C6") (pin "2") (pinfunction "2_2") (pintype "passive"))
      (node (ref "J2") (pin "13") (pinfunction "13_13") (pintype "bidirectional"))
      (node (ref "J2") (pin "14") (pinfunction "14_14") (pintype "bidirectional"))
      (node (ref "J2") (pin "15") (pinfunction "15_15") (pintype "bidirectional"))
      (node (ref "J2") (pin "16") (pinfunction "16_16") (pintype "bidirectional"))
      (node (ref "R1") (pin "2") (pinfunction "2_2") (pintype "passive"))
      (node (ref "R22") (pin "1") (pinfunction "1_1") (pintype "passive"))
    )
    (net (code "36") (name "Net-(AD9201-REFB-I)") (class "Default")
      (node (ref "AD9201") (pin "19") (pinfunction "REFB-I_19") (pintype "bidirectional"))
      (node (ref "C28") (pin "2") (pinfunction "2_2") (pintype "passive"))
      (node (ref "C31") (pin "2") (pinfunction "2_2") (pintype "passive"))
      (node (ref "C7") (pin "2") (pinfunction "2_2") (pintype "passive"))
    )
    (net (code "37") (name "Net-(AD9201-REFT-I)") (class "Default")
      (node (ref "AD9201") (pin "18") (pinfunction "REFT-I_18") (pintype "bidirectional"))
      (node (ref "C13") (pin "2") (pinfunction "2_2") (pintype "passive"))
      (node (ref "C28") (pin "1") (pinfunction "1_1") (pintype "passive"))
      (node (ref "C31") (pin "1") (pinfunction "1_1") (pintype "passive"))
    )
    (net (code "38") (name "Net-(AD9201-VREF)") (class "Default")
      (node (ref "AD9201") (pin "22") (pinfunction "VREF_22") (pintype "output"))
      (node (ref "C29") (pin "2") (pinfunction "2_2") (pintype "passive"))
      (node (ref "C5") (pin "2") (pinfunction "2_2") (pintype "passive"))
      (node (ref "R1") (pin "1") (pinfunction "1_1") (pintype "passive"))
    )
    (net (code "39") (name "Net-(AMUX0-COM)") (class "Default")
      (node (ref "AMUX0") (pin "P$8") (pinfunction "COM_P$8") (pintype "bidirectional"))
      (node (ref "R15") (pin "2") (pinfunction "2_2") (pintype "passive"))
    )
    (net (code "40") (name "Net-(AMUX0-NO0)") (class "Default")
      (node (ref "AMUX0") (pin "P$2") (pinfunction "NO0_P$2") (pintype "bidirectional"))
      (node (ref "J2") (pin "8") (pinfunction "8_8") (pintype "bidirectional"))
    )
    (net (code "41") (name "Net-(AMUX0-NO1)") (class "Default")
      (node (ref "AMUX0") (pin "P$9") (pinfunction "NO1_P$9") (pintype "bidirectional"))
      (node (ref "J2") (pin "7") (pinfunction "7_7") (pintype "bidirectional"))
    )
    (net (code "42") (name "Net-(AMUX0-NO2)") (class "Default")
      (node (ref "AMUX0") (pin "P$4") (pinfunction "NO2_P$4") (pintype "bidirectional"))
      (node (ref "J2") (pin "6") (pinfunction "6_6") (pintype "bidirectional"))
    )
    (net (code "43") (name "Net-(AMUX0-NO3)") (class "Default")
      (node (ref "AMUX0") (pin "P$7") (pinfunction "NO3_P$7") (pintype "bidirectional"))
      (node (ref "J2") (pin "5") (pinfunction "5_5") (pintype "bidirectional"))
    )
    (net (code "44") (name "Net-(AMUX1-COM)") (class "Default")
      (node (ref "AMUX1") (pin "P$8") (pinfunction "COM_P$8") (pintype "bidirectional"))
      (node (ref "R14") (pin "2") (pinfunction "2_2") (pintype "passive"))
    )
    (net (code "45") (name "Net-(AMUX1-NO0)") (class "Default")
      (node (ref "AMUX1") (pin "P$2") (pinfunction "NO0_P$2") (pintype "bidirectional"))
      (node (ref "J2") (pin "4") (pinfunction "4_4") (pintype "bidirectional"))
    )
    (net (code "46") (name "Net-(AMUX1-NO1)") (class "Default")
      (node (ref "AMUX1") (pin "P$9") (pinfunction "NO1_P$9") (pintype "bidirectional"))
      (node (ref "J2") (pin "3") (pinfunction "3_3") (pintype "bidirectional"))
    )
    (net (code "47") (name "Net-(AMUX1-NO2)") (class "Default")
      (node (ref "AMUX1") (pin "P$4") (pinfunction "NO2_P$4") (pintype "bidirectional"))
      (node (ref "J2") (pin "2") (pinfunction "2_2") (pintype "bidirectional"))
    )
    (net (code "48") (name "Net-(AMUX1-NO3)") (class "Default")
      (node (ref "AMUX1") (pin "P$7") (pinfunction "NO3_P$7") (pintype "bidirectional"))
      (node (ref "J2") (pin "1") (pinfunction "1_1") (pintype "bidirectional"))
    )
    (net (code "49") (name "Net-(D1-Pad+)") (class "Default")
      (node (ref "D1") (pin "+") (pinfunction "+_+") (pintype "passive"))
      (node (ref "R19") (pin "2") (pinfunction "2_2") (pintype "passive"))
    )
    (net (code "50") (name "Net-(D2-Pad-)") (class "Default")
      (node (ref "D2") (pin "-") (pinfunction "-_-") (pintype "passive"))
      (node (ref "R21") (pin "2") (pinfunction "2_2") (pintype "passive"))
    )
    (net (code "51") (name "Net-(D3-Pad-)") (class "Default")
      (node (ref "D3") (pin "-") (pinfunction "-_-") (pintype "passive"))
      (node (ref "R28") (pin "2") (pinfunction "2_2") (pintype "passive"))
    )
    (net (code "52") (name "Net-(J1-P$1)") (class "Default")
      (node (ref "J1") (pin "1") (pinfunction "P$1_1") (pintype "bidirectional"))
      (node (ref "U$4") (pin "P3") (pinfunction "CLOCK_P3") (pintype "bidirectional"))
    )
    (net (code "53") (name "Net-(J1-P$3)") (class "Default")
      (node (ref "J1") (pin "3") (pinfunction "P$3_3") (pintype "bidirectional"))
      (node (ref "U$2") (pin "P9.31") (pinfunction "GPIO_120_P9.31") (pintype "bidirectional"))
    )
    (net (code "54") (name "Net-(J4-Pad2)") (class "Default")
      (node (ref "J4") (pin "2") (pinfunction "2_2") (pintype "bidirectional"))
      (node (ref "R18") (pin "2") (pinfunction "2_2") (pintype "passive"))
    )
    (net (code "55") (name "Net-(J5-Pad1)") (class "Default")
      (node (ref "J5") (pin "1") (pinfunction "1_1") (pintype "bidirectional"))
      (node (ref "R2") (pin "2") (pinfunction "2_2") (pintype "passive"))
      (node (ref "RAW1") (pin "1") (pinfunction "1_1") (pintype "passive"))
    )
    (net (code "56") (name "Net-(J5-Pad2)") (class "Default")
      (node (ref "J5") (pin "2") (pinfunction "2_2") (pintype "bidirectional"))
      (node (ref "R17") (pin "2") (pinfunction "2_2") (pintype "passive"))
    )
    (net (code "57") (name "Net-(J6-Pad1)") (class "Default")
      (node (ref "J6") (pin "1") (pinfunction "1_1") (pintype "bidirectional"))
      (node (ref "R3") (pin "2") (pinfunction "2_2") (pintype "passive"))
      (node (ref "RAW0") (pin "1") (pinfunction "1_1") (pintype "passive"))
    )
    (net (code "58") (name "Net-(J6-Pad2)") (class "Default")
      (node (ref "J6") (pin "2") (pinfunction "2_2") (pintype "bidirectional"))
      (node (ref "R23") (pin "2") (pinfunction "2_2") (pintype "passive"))
    )
    (net (code "59") (name "Net-(L1-Pad2)") (class "Default")
      (node (ref "L1") (pin "2") (pinfunction "2_2") (pintype "passive"))
      (node (ref "L2") (pin "1") (pinfunction "1_1") (pintype "passive"))
      (node (ref "U$2") (pin "P9.7") (pinfunction "SYS_5V_P9.7") (pintype "bidirectional"))
      (node (ref "U$2") (pin "P9.8") (pinfunction "SYS_5V_P9.8") (pintype "bidirectional"))
    )
    (net (code "60") (name "Net-(U$2B-GPIO_121)") (class "Default")
      (node (ref "R27") (pin "2") (pinfunction "2_2") (pintype "passive"))
      (node (ref "U$2") (pin "P9.29") (pinfunction "GPIO_121_P9.29") (pintype "bidirectional"))
    )
    (net (code "61") (name "Net-(U$2B-GPIO_122)") (class "Default")
      (node (ref "R25") (pin "1") (pinfunction "1_1") (pintype "passive"))
      (node (ref "U$2") (pin "P9.26") (pinfunction "GPIO_14_P9.26") (pintype "bidirectional"))
      (node (ref "U$2") (pin "P9.30") (pinfunction "GPIO_122_P9.30") (pintype "bidirectional"))
    )
    (net (code "62") (name "Net-(U$2B-GPIO_123)") (class "Default")
      (node (ref "R24") (pin "1") (pinfunction "1_1") (pintype "passive"))
      (node (ref "U$2") (pin "P9.28") (pinfunction "GPIO_123_P9.28") (pintype "bidirectional"))
    )
    (net (code "63") (name "Net-(U$2B-GPIO_125)") (class "Default")
      (node (ref "R26") (pin "2") (pinfunction "2_2") (pintype "passive"))
      (node (ref "U$2") (pin "P9.27") (pinfunction "GPIO_125_P9.27") (pintype "bidirectional"))
    )
    (net (code "64") (name "Net-(U2-CE)") (class "Default")
      (node (ref "U$3") (pin "2") (pinfunction "2_2") (pintype "passive"))
      (node (ref "U2") (pin "3") (pinfunction "CE_3") (pintype "bidirectional"))
    )
    (net (code "65") (name "Net-(U3-CE)") (class "Default")
      (node (ref "U$1") (pin "2") (pinfunction "2_2") (pintype "passive"))
      (node (ref "U3") (pin "3") (pinfunction "CE_3") (pintype "bidirectional"))
    )
    (net (code "66") (name "unconnected-(AD9201-REFB-Q-Pad24)") (class "Default")
      (node (ref "AD9201") (pin "24") (pinfunction "REFB-Q_24") (pintype "bidirectional"))
    )
    (net (code "67") (name "unconnected-(AD9201-REFT-Q-Pad25)") (class "Default")
      (node (ref "AD9201") (pin "25") (pinfunction "REFT-Q_25") (pintype "bidirectional"))
    )
    (net (code "68") (name "unconnected-(U$2A-GPIO_8-PadP8.35)") (class "Default")
      (node (ref "U$2") (pin "P8.35") (pinfunction "GPIO_8_P8.35") (pintype "bidirectional"))
    )
    (net (code "69") (name "unconnected-(U$2A-GPIO_9-PadP8.33)") (class "Default")
      (node (ref "U$2") (pin "P8.33") (pinfunction "GPIO_9_P8.33") (pintype "bidirectional"))
    )
    (net (code "70") (name "unconnected-(U$2A-GPIO_10-PadP8.31)") (class "Default")
      (node (ref "U$2") (pin "P8.31") (pinfunction "GPIO_10_P8.31") (pintype "bidirectional"))
    )
    (net (code "71") (name "unconnected-(U$2A-GPIO_11-PadP8.32)") (class "Default")
      (node (ref "U$2") (pin "P8.32") (pinfunction "GPIO_11_P8.32") (pintype "bidirectional"))
    )
    (net (code "72") (name "unconnected-(U$2A-GPIO_22-PadP8.19)") (class "Default")
      (node (ref "U$2") (pin "P8.19") (pinfunction "GPIO_22_P8.19") (pintype "bidirectional"))
    )
    (net (code "73") (name "unconnected-(U$2A-GPIO_23-PadP8.13)") (class "Default")
      (node (ref "U$2") (pin "P8.13") (pinfunction "GPIO_23_P8.13") (pintype "bidirectional"))
    )
    (net (code "74") (name "unconnected-(U$2A-GPIO_26-PadP8.14)") (class "Default")
      (node (ref "U$2") (pin "P8.14") (pinfunction "GPIO_26_P8.14") (pintype "bidirectional"))
    )
    (net (code "75") (name "unconnected-(U$2A-GPIO_27-PadP8.17)") (class "Default")
      (node (ref "U$2") (pin "P8.17") (pinfunction "GPIO_27_P8.17") (pintype "bidirectional"))
    )
    (net (code "76") (name "unconnected-(U$2A-GPIO_32-PadP8.25)") (class "Default")
      (node (ref "U$2") (pin "P8.25") (pinfunction "GPIO_32_P8.25") (pintype "bidirectional"))
    )
    (net (code "77") (name "unconnected-(U$2A-GPIO_33-PadP8.24)") (class "Default")
      (node (ref "U$2") (pin "P8.24") (pinfunction "GPIO_33_P8.24") (pintype "bidirectional"))
    )
    (net (code "78") (name "unconnected-(U$2A-GPIO_34-PadP8.5)") (class "Default")
      (node (ref "U$2") (pin "P8.5") (pinfunction "GPIO_34_P8.5") (pintype "bidirectional"))
    )
    (net (code "79") (name "unconnected-(U$2A-GPIO_35-PadP8.6)") (class "Default")
      (node (ref "U$2") (pin "P8.6") (pinfunction "GPIO_35_P8.6") (pintype "bidirectional"))
    )
    (net (code "80") (name "unconnected-(U$2A-GPIO_36-PadP8.23)") (class "Default")
      (node (ref "U$2") (pin "P8.23") (pinfunction "GPIO_36_P8.23") (pintype "bidirectional"))
    )
    (net (code "81") (name "unconnected-(U$2A-GPIO_37-PadP8.22)") (class "Default")
      (node (ref "U$2") (pin "P8.22") (pinfunction "GPIO_37_P8.22") (pintype "bidirectional"))
    )
    (net (code "82") (name "unconnected-(U$2A-GPIO_38-PadP8.3)") (class "Default")
      (node (ref "U$2") (pin "P8.3") (pinfunction "GPIO_38_P8.3") (pintype "bidirectional"))
    )
    (net (code "83") (name "unconnected-(U$2A-GPIO_39-PadP8.4)") (class "Default")
      (node (ref "U$2") (pin "P8.4") (pinfunction "GPIO_39_P8.4") (pintype "bidirectional"))
    )
    (net (code "84") (name "unconnected-(U$2A-GPIO_44-PadP8.12)") (class "Default")
      (node (ref "U$2") (pin "P8.12") (pinfunction "GPIO_44_P8.12") (pintype "bidirectional"))
    )
    (net (code "85") (name "unconnected-(U$2A-GPIO_45-PadP8.11)") (class "Default")
      (node (ref "U$2") (pin "P8.11") (pinfunction "GPIO_45_P8.11") (pintype "bidirectional"))
    )
    (net (code "86") (name "unconnected-(U$2A-GPIO_46-PadP8.16)") (class "Default")
      (node (ref "U$2") (pin "P8.16") (pinfunction "GPIO_46_P8.16") (pintype "bidirectional"))
    )
    (net (code "87") (name "unconnected-(U$2A-GPIO_47-PadP8.15)") (class "Default")
      (node (ref "U$2") (pin "P8.15") (pinfunction "GPIO_47_P8.15") (pintype "bidirectional"))
    )
    (net (code "88") (name "unconnected-(U$2A-GPIO_61-PadP8.26)") (class "Default")
      (node (ref "U$2") (pin "P8.26") (pinfunction "GPIO_61_P8.26") (pintype "bidirectional"))
    )
    (net (code "89") (name "unconnected-(U$2A-GPIO_62-PadP8.21)") (class "Default")
      (node (ref "U$2") (pin "P8.21") (pinfunction "GPIO_62_P8.21") (pintype "bidirectional"))
    )
    (net (code "90") (name "unconnected-(U$2A-GPIO_63-PadP8.20)") (class "Default")
      (node (ref "U$2") (pin "P8.20") (pinfunction "GPIO_63_P8.20") (pintype "bidirectional"))
    )
    (net (code "91") (name "unconnected-(U$2A-GPIO_65-PadP8.18)") (class "Default")
      (node (ref "U$2") (pin "P8.18") (pinfunction "GPIO_65_P8.18") (pintype "bidirectional"))
    )
    (net (code "92") (name "unconnected-(U$2A-GPIO_66-PadP8.7)") (class "Default")
      (node (ref "U$2") (pin "P8.7") (pinfunction "GPIO_66_P8.7") (pintype "bidirectional"))
    )
    (net (code "93") (name "unconnected-(U$2A-GPIO_67-PadP8.8)") (class "Default")
      (node (ref "U$2") (pin "P8.8") (pinfunction "GPIO_67_P8.8") (pintype "bidirectional"))
    )
    (net (code "94") (name "unconnected-(U$2A-GPIO_68-PadP8.10)") (class "Default")
      (node (ref "U$2") (pin "P8.10") (pinfunction "GPIO_68_P8.10") (pintype "bidirectional"))
    )
    (net (code "95") (name "unconnected-(U$2A-GPIO_69-PadP8.9)") (class "Default")
      (node (ref "U$2") (pin "P8.9") (pinfunction "GPIO_69_P8.9") (pintype "bidirectional"))
    )
    (net (code "96") (name "unconnected-(U$2A-GPIO_78-PadP8.37)") (class "Default")
      (node (ref "U$2") (pin "P8.37") (pinfunction "GPIO_78_P8.37") (pintype "bidirectional"))
    )
    (net (code "97") (name "unconnected-(U$2A-GPIO_79-PadP8.38)") (class "Default")
      (node (ref "U$2") (pin "P8.38") (pinfunction "GPIO_79_P8.38") (pintype "bidirectional"))
    )
    (net (code "98") (name "unconnected-(U$2A-GPIO_80-PadP8.36)") (class "Default")
      (node (ref "U$2") (pin "P8.36") (pinfunction "GPIO_80_P8.36") (pintype "bidirectional"))
    )
    (net (code "99") (name "unconnected-(U$2A-GPIO_81-PadP8.34)") (class "Default")
      (node (ref "U$2") (pin "P8.34") (pinfunction "GPIO_81_P8.34") (pintype "bidirectional"))
    )
    (net (code "100") (name "unconnected-(U$2B-AIN0-PadP9.39)") (class "Default")
      (node (ref "U$2") (pin "P9.39") (pinfunction "AIN0_P9.39") (pintype "bidirectional"))
    )
    (net (code "101") (name "unconnected-(U$2B-AIN1-PadP9.40)") (class "Default")
      (node (ref "U$2") (pin "P9.40") (pinfunction "AIN1_P9.40") (pintype "bidirectional"))
    )
    (net (code "102") (name "unconnected-(U$2B-AIN2-PadP9.37)") (class "Default")
      (node (ref "U$2") (pin "P9.37") (pinfunction "AIN2_P9.37") (pintype "bidirectional"))
    )
    (net (code "103") (name "unconnected-(U$2B-AIN3-PadP9.38)") (class "Default")
      (node (ref "U$2") (pin "P9.38") (pinfunction "AIN3_P9.38") (pintype "bidirectional"))
    )
    (net (code "104") (name "unconnected-(U$2B-AIN4-PadP9.33)") (class "Default")
      (node (ref "U$2") (pin "P9.33") (pinfunction "AIN4_P9.33") (pintype "bidirectional"))
    )
    (net (code "105") (name "unconnected-(U$2B-AIN5-PadP9.36)") (class "Default")
      (node (ref "U$2") (pin "P9.36") (pinfunction "AIN5_P9.36") (pintype "bidirectional"))
    )
    (net (code "106") (name "unconnected-(U$2B-AIN6-PadP9.35)") (class "Default")
      (node (ref "U$2") (pin "P9.35") (pinfunction "AIN6_P9.35") (pintype "bidirectional"))
    )
    (net (code "107") (name "unconnected-(U$2B-DGND-PadP9.44)") (class "Default")
      (node (ref "U$2") (pin "P9.44") (pinfunction "DGND_P9.44") (pintype "bidirectional"))
    )
    (net (code "108") (name "unconnected-(U$2B-GNDA_ADC-PadP9.34)") (class "Default")
      (node (ref "U$2") (pin "P9.34") (pinfunction "GNDA_ADC_P9.34") (pintype "bidirectional"))
    )
    (net (code "109") (name "unconnected-(U$2B-GPIO_2-PadP9.22)") (class "Default")
      (node (ref "U$2") (pin "P9.22") (pinfunction "GPIO_2_P9.22") (pintype "bidirectional"))
    )
    (net (code "110") (name "unconnected-(U$2B-GPIO_3-PadP9.21)") (class "Default")
      (node (ref "U$2") (pin "P9.21") (pinfunction "GPIO_3_P9.21") (pintype "bidirectional"))
    )
    (net (code "111") (name "unconnected-(U$2B-GPIO_4-PadP9.17)") (class "Default")
      (node (ref "U$2") (pin "P9.17") (pinfunction "GPIO_4_P9.17") (pintype "bidirectional"))
    )
    (net (code "112") (name "unconnected-(U$2B-GPIO_5-PadP9.18)") (class "Default")
      (node (ref "U$2") (pin "P9.18") (pinfunction "GPIO_5_P9.18") (pintype "bidirectional"))
    )
    (net (code "113") (name "unconnected-(U$2B-GPIO_7-PadP9.42)") (class "Default")
      (node (ref "U$2") (pin "P9.42") (pinfunction "GPIO_7_P9.42") (pintype "bidirectional"))
    )
    (net (code "114") (name "unconnected-(U$2B-GPIO_15-PadP9.24)") (class "Default")
      (node (ref "U$2") (pin "P9.24") (pinfunction "GPIO_15_P9.24") (pintype "bidirectional"))
    )
    (net (code "115") (name "unconnected-(U$2B-GPIO_20-PadP9.41)") (class "Default")
      (node (ref "U$2") (pin "P9.41") (pinfunction "GPIO_20_P9.41") (pintype "bidirectional"))
    )
    (net (code "116") (name "unconnected-(U$2B-GPIO_30-PadP9.11)") (class "Default")
      (node (ref "U$2") (pin "P9.11") (pinfunction "GPIO_30_P9.11") (pintype "bidirectional"))
    )
    (net (code "117") (name "unconnected-(U$2B-GPIO_31-PadP9.13)") (class "Default")
      (node (ref "U$2") (pin "P9.13") (pinfunction "GPIO_31_P9.13") (pintype "bidirectional"))
    )
    (net (code "118") (name "unconnected-(U$2B-GPIO_40-PadP9.14)") (class "Default")
      (node (ref "U$2") (pin "P9.14") (pinfunction "GPIO_40_P9.14") (pintype "bidirectional"))
    )
    (net (code "119") (name "unconnected-(U$2B-GPIO_48-PadP9.15)") (class "Default")
      (node (ref "U$2") (pin "P9.15") (pinfunction "GPIO_48_P9.15") (pintype "bidirectional"))
    )
    (net (code "120") (name "unconnected-(U$2B-GPIO_49-PadP9.23)") (class "Default")
      (node (ref "U$2") (pin "P9.23") (pinfunction "GPIO_49_P9.23") (pintype "bidirectional"))
    )
    (net (code "121") (name "unconnected-(U$2B-GPIO_51-PadP9.16)") (class "Default")
      (node (ref "U$2") (pin "P9.16") (pinfunction "GPIO_51_P9.16") (pintype "bidirectional"))
    )
    (net (code "122") (name "unconnected-(U$2B-GPIO_60-PadP9.12)") (class "Default")
      (node (ref "U$2") (pin "P9.12") (pinfunction "GPIO_60_P9.12") (pintype "bidirectional"))
    )
    (net (code "123") (name "unconnected-(U$2B-I2C2_SCL-PadP9.19)") (class "Default")
      (node (ref "U$2") (pin "P9.19") (pinfunction "I2C2_SCL_P9.19") (pintype "bidirectional"))
    )
    (net (code "124") (name "unconnected-(U$2B-I2C2_SDA-PadP9.20)") (class "Default")
      (node (ref "U$2") (pin "P9.20") (pinfunction "I2C2_SDA_P9.20") (pintype "bidirectional"))
    )
    (net (code "125") (name "unconnected-(U$2B-PWR_BUT-PadP9.9)") (class "Default")
      (node (ref "U$2") (pin "P9.9") (pinfunction "PWR_BUT_P9.9") (pintype "bidirectional"))
    )
    (net (code "126") (name "unconnected-(U$2B-SYS_RESET~{N}-PadP9.10)") (class "Default")
      (node (ref "U$2") (pin "P9.10") (pinfunction "SYS_RESET~{N}_P9.10") (pintype "bidirectional"))
    )
    (net (code "127") (name "unconnected-(U$2B-VDD_3V3-PadP9.3)") (class "Default")
      (node (ref "U$2") (pin "P9.3") (pinfunction "VDD_3V3_P9.3") (pintype "bidirectional"))
    )
    (net (code "128") (name "unconnected-(U$2B-VDD_3V3-PadP9.4)") (class "Default")
      (node (ref "U$2") (pin "P9.4") (pinfunction "VDD_3V3_P9.4") (pintype "bidirectional"))
    )
    (net (code "129") (name "unconnected-(U$2B-VDD_5V-PadP9.5)") (class "Default")
      (node (ref "U$2") (pin "P9.5") (pinfunction "VDD_5V_P9.5") (pintype "bidirectional"))
    )
    (net (code "130") (name "unconnected-(U$2B-VDD_5V-PadP9.6)") (class "Default")
      (node (ref "U$2") (pin "P9.6") (pinfunction "VDD_5V_P9.6") (pintype "bidirectional"))
    )
    (net (code "131") (name "unconnected-(U$2B-VDD_ADC-PadP9.32)") (class "Default")
      (node (ref "U$2") (pin "P9.32") (pinfunction "VDD_ADC_P9.32") (pintype "bidirectional"))
    )
  )
)
